# Low_pass_filter.net
KiCad netlist of a schematic drawn in EAGLE
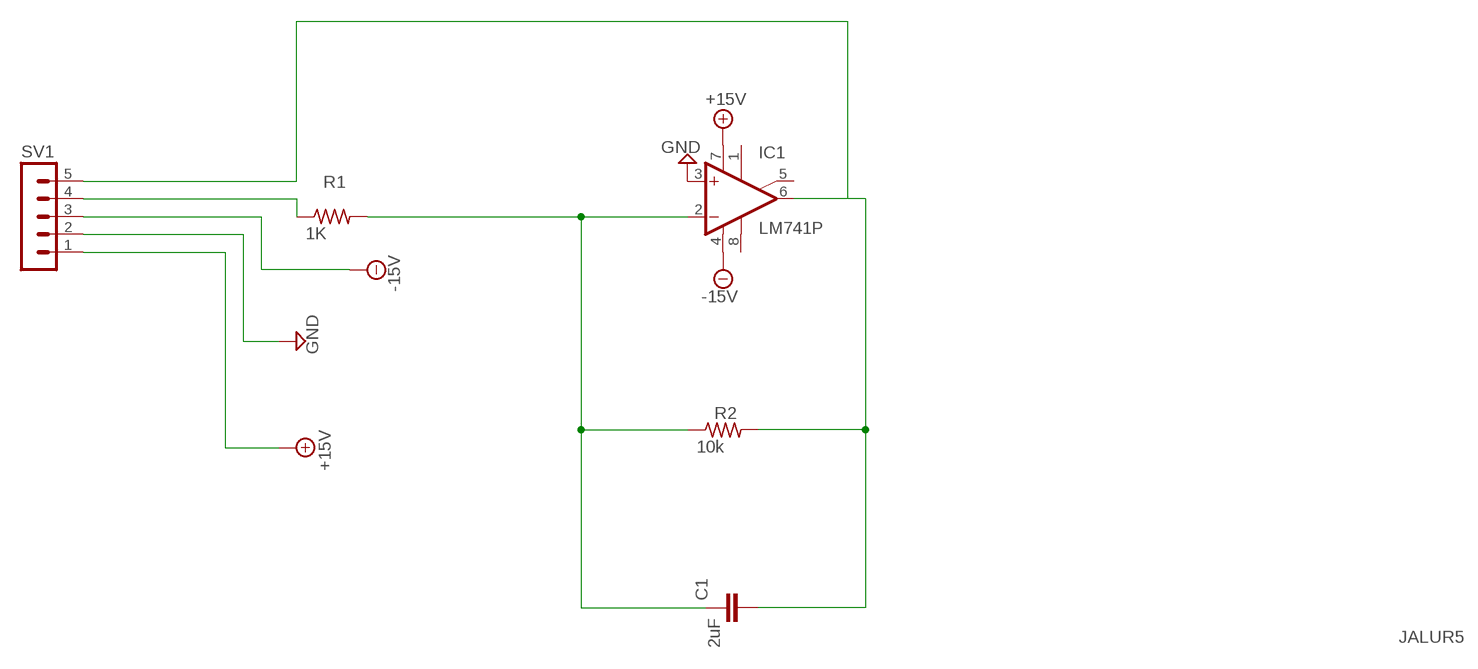
[diagram p0: schematic, sheet 1]

(export (version "E")
  (design (tool "Eeschema 10.0.6"))
  (components
    (comp (ref "C1")
      (value "2uF")
      (footprint "eagle-import:C0603")
      (libsource (lib "eagle-import") (part "C-EUC0603"))
    )
    (comp (ref "IC1")
      (value "LM741P")
      (footprint "eagle-import:DIL08")
      (libsource (lib "eagle-import") (part "741PLM"))
    )
    (comp (ref "R1")
      (value "1K")
      (footprint "eagle-import:R0603")
      (libsource (lib "eagle-import") (part "R-US_R0603"))
    )
    (comp (ref "R2")
      (value "10k")
      (footprint "eagle-import:R0603")
      (libsource (lib "eagle-import") (part "R-US_R0603"))
    )
    (comp (ref "SV1")
      (value "MA05-1")
      (footprint "eagle-import:MA05-1")
      (libsource (lib "eagle-import") (part "MA05-1"))
    )
  )
  (nets
    (net (code "1") (name "+15V") (class "Default")
      (node (ref "IC1") (pin "7") (pinfunction "V+_7") (pintype "power_in"))
      (node (ref "SV1") (pin "1") (pinfunction "1_1") (pintype "passive"))
    )
    (net (code "2") (name "-15V") (class "Default")
      (node (ref "IC1") (pin "4") (pinfunction "V-_4") (pintype "power_in"))
      (node (ref "SV1") (pin "3") (pinfunction "3_3") (pintype "passive"))
    )
    (net (code "3") (name "/JALUR5") (class "Default")
      (node (ref "C1") (pin "1") (pinfunction "1_1") (pintype "passive"))
      (node (ref "IC1") (pin "6") (pinfunction "OUT_6") (pintype "output"))
      (node (ref "R2") (pin "2") (pinfunction "2_2") (pintype "passive"))
      (node (ref "SV1") (pin "5") (pinfunction "5_5") (pintype "passive"))
    )
    (net (code "4") (name "GND") (class "Default")
      (node (ref "IC1") (pin "3") (pinfunction "+IN_3") (pintype "input"))
      (node (ref "SV1") (pin "2") (pinfunction "2_2") (pintype "passive"))
    )
    (net (code "5") (name "Net-(IC1--IN)") (class "Default")
      (node (ref "C1") (pin "2") (pinfunction "2_2") (pintype "passive"))
      (node (ref "IC1") (pin "2") (pinfunction "-IN_2") (pintype "input"))
      (node (ref "R1") (pin "2") (pinfunction "2_2") (pintype "passive"))
      (node (ref "R2") (pin "1") (pinfunction "1_1") (pintype "passive"))
    )
    (net (code "6") (name "Net-(R1-Pad1)") (class "Default")
      (node (ref "R1") (pin "1") (pinfunction "1_1") (pintype "passive"))
      (node (ref "SV1") (pin "4") (pinfunction "4_4") (pintype "passive"))
    )
    (net (code "7") (name "unconnected-(IC1-ON1-Pad1)") (class "Default")
      (node (ref "IC1") (pin "1") (pinfunction "ON1_1") (pintype "passive"))
    )
    (net (code "8") (name "unconnected-(IC1-ON2-Pad5)") (class "Default")
      (node (ref "IC1") (pin "5") (pinfunction "ON2_5") (pintype "passive"))
    )
    (net (code "9") (name "unconnected-(IC1-OPT-Pad8)") (class "Default")
      (node (ref "IC1") (pin "8") (pinfunction "OPT_8") (pintype "passive"))
    )
  )
)
